# Boost-converter.net
KiCad netlist of a schematic drawn in Altium Designer
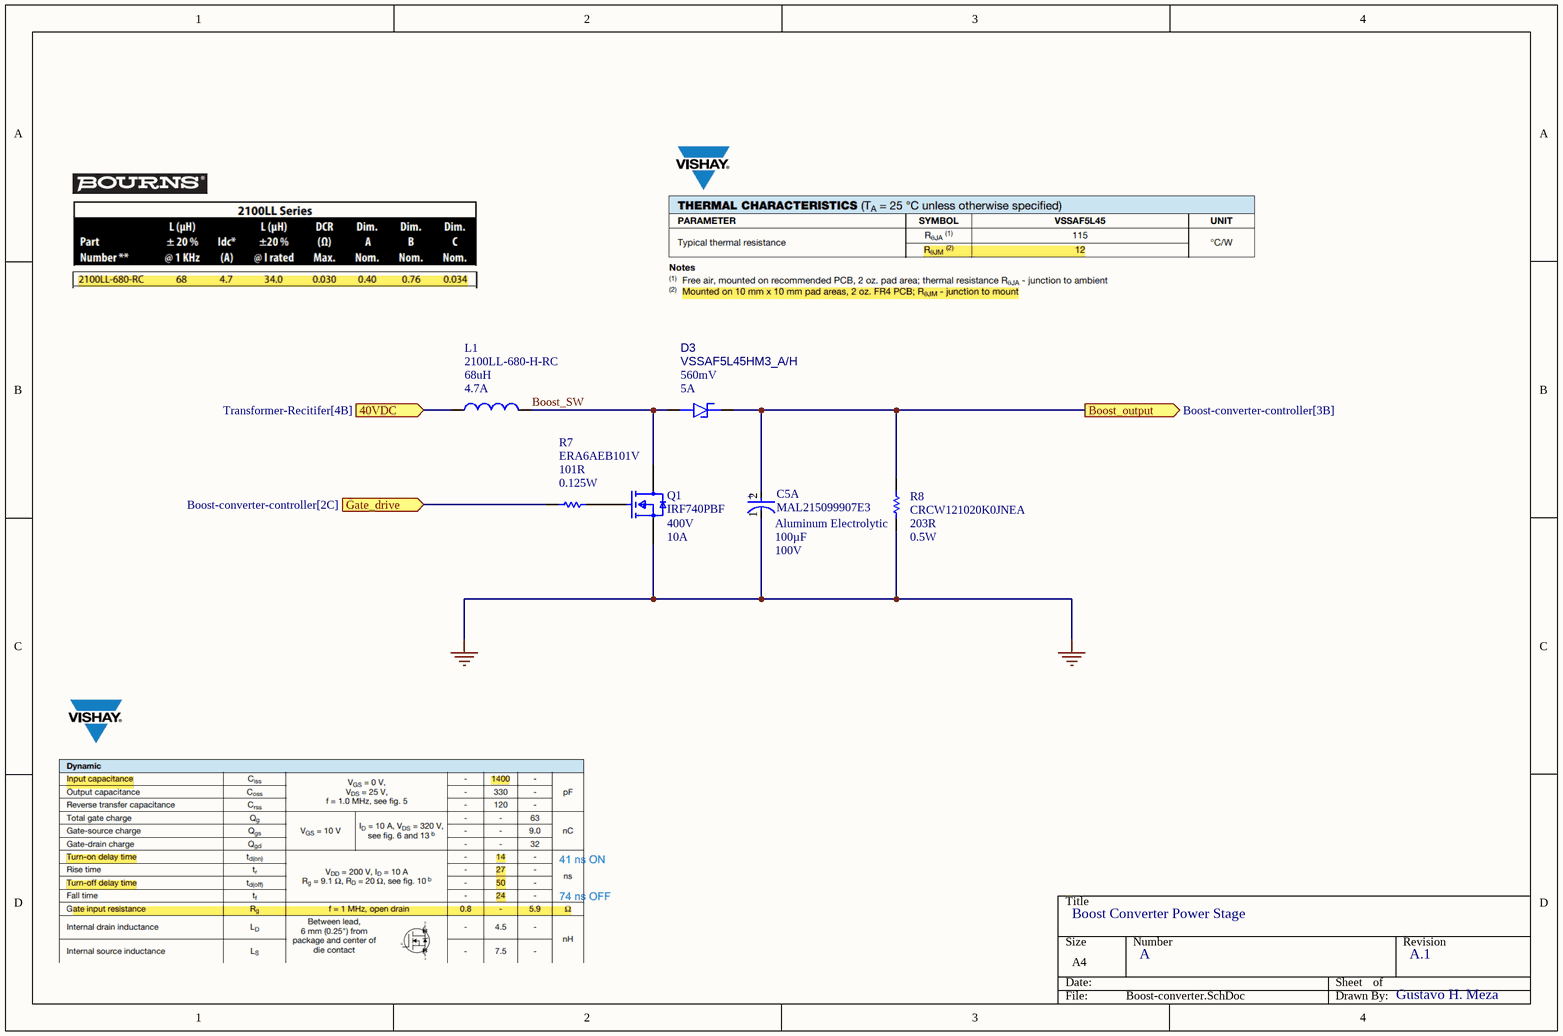
[diagram p0: Boost-converter.SchDoc]

(export (version "E")
  (design (tool "Eeschema 10.0.6"))
  (components
    (comp (ref "C5")
      (value "MAL215099907E3")
      (footprint "FP-MAL215099907E3-MFG")
      (fields
        (field (name "VOLTAGE RATING") "100V")
        (field (name "CAPACITANCE") "100µF")
        (field (name "TOLERANCE") "20%")
        (field (name "CONSTRUCTION") "Aluminum Electrolytic")
      )
      (libsource (lib "Altium Content Vault") (part "c6cab7c05467c2c24ca61f0f00c062c"))
    )
    (comp (ref "D3")
      (value "VSSAF5L45HM3_A/H")
      (footprint "VSSAF5L45HM3_A_H-Footprint-1")
      (description "Diode Schottky 45V 5A DO221AC")
      (fields (field (name "FORWARD CURRENT") "5A") (field (name "FORWARD VOLTAGE") "560mV"))
      (libsource (lib "Cetys University") (part "DIODE-2"))
    )
    (comp (ref "L1")
      (value "2100LL-680-H-RC")
      (footprint "2100LL-680-H-RC-Footprint-1")
      (description "General Purpose Inductor, 68uH, 15%, 1 Element")
      (fields
        (field (name "INDUCTANCE-NOM (L)") "68uH")
        (field (name "TOLERANCE") "15%")
        (field (name "MAX CURRENT RATING") "4.7A")
      )
      (libsource (lib "Cetys University") (part "IND-2"))
    )
    (comp (ref "Q1")
      (value "IRF740PBF")
      (footprint "FP-X15-0364-MFG")
      (description "MOSFET N-CH 400V 10A TO-220AB")
      (fields
        (field (name "DRAIN TO SOURCE VOLTAGE") "400V")
        (field (name "CONTINUOUS DRAIN CURRENT") "10A")
        (field (name "OCTOPART") "https://octopart.com/irf740pbf-vishay-46527100")
        (field (name "MANUFACTURER") "Vishay")
      )
      (libsource (lib "Altium Content Vault") (part "b44c8776e10362b01251f5cff19d373"))
    )
    (comp (ref "R7")
      (value "ERA6AEB101V")
      (footprint "RESC2013X60X40ML20T25")
      (fields
        (field (name "MANUFACTURER") "Panasonic")
        (field (name "RESISTANCE") "101R")
        (field (name "POWER RATING") "0.125W")
      )
      (libsource (lib "Altium Content Vault") (part "RES"))
    )
    (comp (ref "R8")
      (value "CRCW121020K0JNEA")
      (footprint "RESC3225X60X45NL20T20")
      (fields
        (field (name "MANUFACTURER") "Vishay Dale")
        (field (name "RESISTANCE") "203R")
        (field (name "POWER") "0.5W")
      )
      (libsource (lib "Altium Content Vault") (part "RES"))
    )
  )
  (nets
    (net (code "1") (name "/40VDC") (class "Default")
      (node (ref "L1") (pin "1") (pinfunction "1_1") (pintype "passive"))
    )
    (net (code "2") (name "/Boost_SW") (class "Default")
      (node (ref "D3") (pin "2") (pinfunction "A_2") (pintype "passive"))
      (node (ref "L1") (pin "2") (pinfunction "2_2") (pintype "passive"))
      (node (ref "Q1") (pin "2") (pinfunction "D_2") (pintype "passive"))
    )
    (net (code "3") (name "/Boost_output") (class "Default")
      (node (ref "C5") (pin "2") (pinfunction "A_2") (pintype "passive"))
      (node (ref "D3") (pin "1") (pinfunction "K_1") (pintype "passive"))
      (node (ref "R8") (pin "2") (pinfunction "2_2") (pintype "passive"))
    )
    (net (code "4") (name "/Gate_drive") (class "Default")
      (node (ref "R7") (pin "1") (pinfunction "1_1") (pintype "passive"))
    )
    (net (code "5") (name "GND") (class "Default")
      (node (ref "C5") (pin "1") (pinfunction "C_1") (pintype "passive"))
      (node (ref "Q1") (pin "3") (pinfunction "S_3") (pintype "passive"))
      (node (ref "R8") (pin "1") (pinfunction "1_1") (pintype "passive"))
    )
    (net (code "6") (name "Net-(Q1-G)") (class "Default")
      (node (ref "Q1") (pin "1") (pinfunction "G_1") (pintype "passive"))
      (node (ref "R7") (pin "2") (pinfunction "2_2") (pintype "passive"))
    )
  )
)
